# 32.net
KiCad netlist of a schematic drawn in Altium Designer
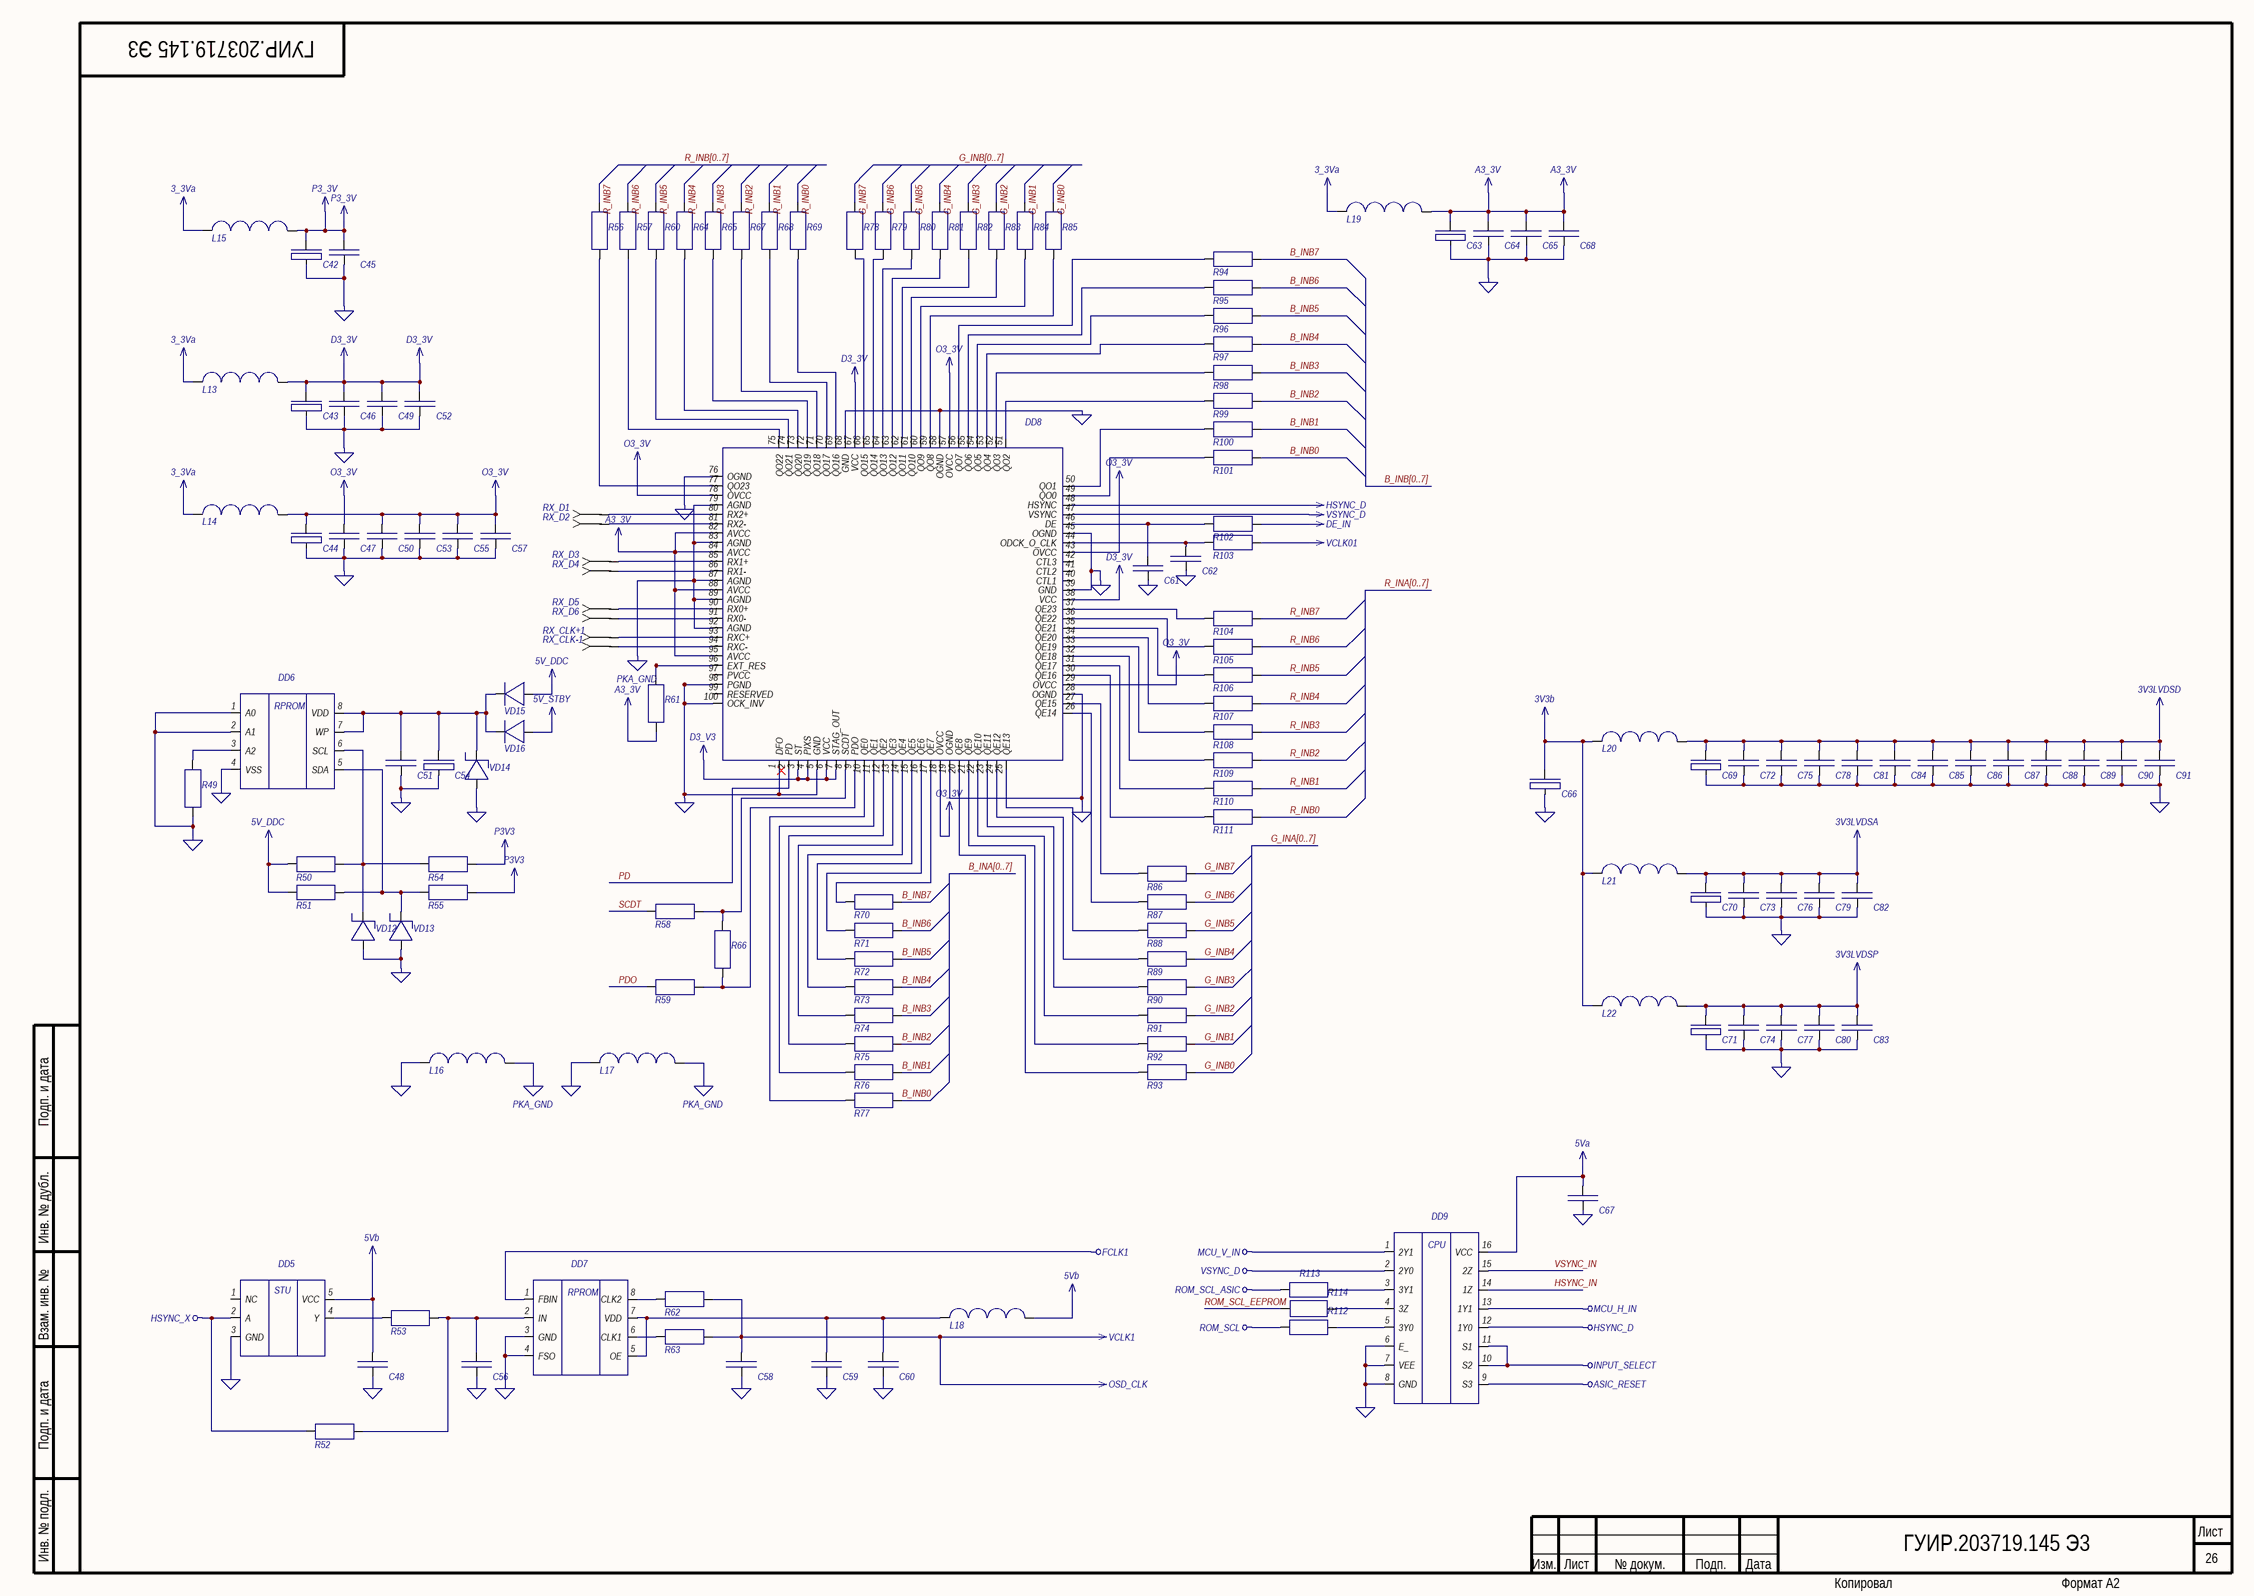
[diagram p0: 32.SchDoc]

(export (version "E")
  (design (tool "Eeschema 10.0.6"))
  (components
    (comp (ref "C42")
      (value "TuningCapacitor")
      (footprint "31_lib:Cap_tantal_D")
      (libsource (lib "31_lib") (part "TuningCapacitor"))
    )
    (comp (ref "C43")
      (value "TuningCapacitor")
      (footprint "31_lib:Cap_tantal_D")
      (libsource (lib "31_lib") (part "TuningCapacitor"))
    )
    (comp (ref "C44")
      (value "TuningCapacitor")
      (footprint "31_lib:Cap_tantal_D")
      (libsource (lib "31_lib") (part "TuningCapacitor"))
    )
    (comp (ref "C45")
      (value "Capacitor")
      (footprint "cap_electro_13")
      (libsource (lib "31_lib") (part "Capacitor"))
    )
    (comp (ref "C46")
      (value "Capacitor")
      (footprint "cap_electro_13")
      (libsource (lib "31_lib") (part "Capacitor"))
    )
    (comp (ref "C47")
      (value "Capacitor")
      (footprint "cap_electro_13")
      (libsource (lib "31_lib") (part "Capacitor"))
    )
    (comp (ref "C48")
      (value "Capacitor")
      (footprint "cap_electro_13")
      (libsource (lib "31_lib") (part "Capacitor"))
    )
    (comp (ref "C49")
      (value "Capacitor")
      (footprint "cap_electro_13")
      (libsource (lib "31_lib") (part "Capacitor"))
    )
    (comp (ref "C50")
      (value "Capacitor")
      (footprint "cap_electro_13")
      (libsource (lib "31_lib") (part "Capacitor"))
    )
    (comp (ref "C51")
      (value "Capacitor")
      (footprint "cap_electro_13")
      (libsource (lib "31_lib") (part "Capacitor"))
    )
    (comp (ref "C52")
      (value "Capacitor")
      (footprint "cap_electro_13")
      (libsource (lib "31_lib") (part "Capacitor"))
    )
    (comp (ref "C53")
      (value "Capacitor")
      (footprint "cap_electro_13")
      (libsource (lib "31_lib") (part "Capacitor"))
    )
    (comp (ref "C54")
      (value "TuningCapacitor")
      (footprint "31_lib:Cap_tantal_D")
      (libsource (lib "31_lib") (part "TuningCapacitor"))
    )
    (comp (ref "C55")
      (value "Capacitor")
      (footprint "cap_electro_13")
      (libsource (lib "31_lib") (part "Capacitor"))
    )
    (comp (ref "C56")
      (value "Capacitor")
      (footprint "cap_electro_13")
      (libsource (lib "31_lib") (part "Capacitor"))
    )
    (comp (ref "C57")
      (value "Capacitor")
      (footprint "cap_electro_13")
      (libsource (lib "31_lib") (part "Capacitor"))
    )
    (comp (ref "C58")
      (value "Capacitor")
      (footprint "cap_electro_13")
      (libsource (lib "31_lib") (part "Capacitor"))
    )
    (comp (ref "C59")
      (value "Capacitor")
      (footprint "cap_electro_13")
      (libsource (lib "31_lib") (part "Capacitor"))
    )
    (comp (ref "C60")
      (value "Capacitor")
      (footprint "cap_electro_13")
      (libsource (lib "31_lib") (part "Capacitor"))
    )
    (comp (ref "C61")
      (value "Capacitor")
      (footprint "cap_electro_13")
      (libsource (lib "31_lib") (part "Capacitor"))
    )
    (comp (ref "C62")
      (value "Capacitor")
      (footprint "cap_electro_13")
      (libsource (lib "31_lib") (part "Capacitor"))
    )
    (comp (ref "C63")
      (value "TuningCapacitor")
      (footprint "31_lib:Cap_tantal_D")
      (libsource (lib "31_lib") (part "TuningCapacitor"))
    )
    (comp (ref "C64")
      (value "Capacitor")
      (footprint "cap_electro_13")
      (libsource (lib "31_lib") (part "Capacitor"))
    )
    (comp (ref "C65")
      (value "Capacitor")
      (footprint "cap_electro_13")
      (libsource (lib "31_lib") (part "Capacitor"))
    )
    (comp (ref "C66")
      (value "TuningCapacitor")
      (footprint "31_lib:Cap_tantal_D")
      (libsource (lib "31_lib") (part "TuningCapacitor"))
    )
    (comp (ref "C67")
      (value "Capacitor")
      (footprint "cap_electro_13")
      (libsource (lib "31_lib") (part "Capacitor"))
    )
    (comp (ref "C68")
      (value "Capacitor")
      (footprint "cap_electro_13")
      (libsource (lib "31_lib") (part "Capacitor"))
    )
    (comp (ref "C69")
      (value "TuningCapacitor")
      (footprint "31_lib:Cap_tantal_D")
      (libsource (lib "31_lib") (part "TuningCapacitor"))
    )
    (comp (ref "C70")
      (value "TuningCapacitor")
      (footprint "31_lib:Cap_tantal_D")
      (libsource (lib "31_lib") (part "TuningCapacitor"))
    )
    (comp (ref "C71")
      (value "TuningCapacitor")
      (footprint "31_lib:Cap_tantal_D")
      (libsource (lib "31_lib") (part "TuningCapacitor"))
    )
    (comp (ref "C72")
      (value "Capacitor")
      (footprint "cap_electro_13")
      (libsource (lib "31_lib") (part "Capacitor"))
    )
    (comp (ref "C73")
      (value "Capacitor")
      (footprint "cap_electro_13")
      (libsource (lib "31_lib") (part "Capacitor"))
    )
    (comp (ref "C74")
      (value "Capacitor")
      (footprint "cap_electro_13")
      (libsource (lib "31_lib") (part "Capacitor"))
    )
    (comp (ref "C75")
      (value "Capacitor")
      (footprint "cap_electro_13")
      (libsource (lib "31_lib") (part "Capacitor"))
    )
    (comp (ref "C76")
      (value "Capacitor")
      (footprint "cap_electro_13")
      (libsource (lib "31_lib") (part "Capacitor"))
    )
    (comp (ref "C77")
      (value "Capacitor")
      (footprint "cap_electro_13")
      (libsource (lib "31_lib") (part "Capacitor"))
    )
    (comp (ref "C78")
      (value "Capacitor")
      (footprint "cap_electro_13")
      (libsource (lib "31_lib") (part "Capacitor"))
    )
    (comp (ref "C79")
      (value "Capacitor")
      (footprint "cap_electro_13")
      (libsource (lib "31_lib") (part "Capacitor"))
    )
    (comp (ref "C80")
      (value "Capacitor")
      (footprint "cap_electro_13")
      (libsource (lib "31_lib") (part "Capacitor"))
    )
    (comp (ref "C81")
      (value "Capacitor")
      (footprint "cap_electro_13")
      (libsource (lib "31_lib") (part "Capacitor"))
    )
    (comp (ref "C82")
      (value "Capacitor")
      (footprint "cap_electro_13")
      (libsource (lib "31_lib") (part "Capacitor"))
    )
    (comp (ref "C83")
      (value "Capacitor")
      (footprint "cap_electro_13")
      (libsource (lib "31_lib") (part "Capacitor"))
    )
    (comp (ref "C84")
      (value "Capacitor")
      (footprint "cap_electro_13")
      (libsource (lib "31_lib") (part "Capacitor"))
    )
    (comp (ref "C85")
      (value "Capacitor")
      (footprint "cap_electro_13")
      (libsource (lib "31_lib") (part "Capacitor"))
    )
    (comp (ref "C86")
      (value "Capacitor")
      (footprint "cap_electro_13")
      (libsource (lib "31_lib") (part "Capacitor"))
    )
    (comp (ref "C87")
      (value "Capacitor")
      (footprint "cap_electro_13")
      (libsource (lib "31_lib") (part "Capacitor"))
    )
    (comp (ref "C88")
      (value "Capacitor")
      (footprint "cap_electro_13")
      (libsource (lib "31_lib") (part "Capacitor"))
    )
    (comp (ref "C89")
      (value "Capacitor")
      (footprint "cap_electro_13")
      (libsource (lib "31_lib") (part "Capacitor"))
    )
    (comp (ref "C90")
      (value "Capacitor")
      (footprint "cap_electro_13")
      (libsource (lib "31_lib") (part "Capacitor"))
    )
    (comp (ref "C91")
      (value "Capacitor")
      (footprint "cap_electro_13")
      (libsource (lib "31_lib") (part "Capacitor"))
    )
    (comp (ref "DD5")
      (value "F14-SINGLE")
      (footprint "74AHC1G14(SOT25)")
      (libsource (lib "31_lib") (part "74AHC1G14-TA"))
    )
    (comp (ref "DD6") (value "24C02") (footprint "31_lib:24Cxx") (libsource (lib "31_lib") (part "24C02")))
    (comp (ref "DD7")
      (value "AV9173-01")
      (footprint "31_lib:AV9173-01(DIP8)")
      (libsource (lib "31_lib") (part "AV9173-01"))
    )
    (comp (ref "DD8") (value "SIL151") (footprint "31_lib:SIL151") (libsource (lib "31_lib") (part "SIL151")))
    (comp (ref "DD9")
      (value "74LV4053")
      (footprint "31_lib:74LV4053(SOT38-4)")
      (libsource (lib "31_lib") (part "74LV4053"))
    )
    (comp (ref "L13")
      (value "Inductor")
      (footprint "31_lib:inductor")
      (libsource (lib "31_lib") (part "Inductor"))
    )
    (comp (ref "L14")
      (value "Inductor")
      (footprint "31_lib:inductor")
      (libsource (lib "31_lib") (part "Inductor"))
    )
    (comp (ref "L15")
      (value "Inductor")
      (footprint "31_lib:inductor")
      (libsource (lib "31_lib") (part "Inductor"))
    )
    (comp (ref "L16")
      (value "Inductor")
      (footprint "31_lib:inductor")
      (libsource (lib "31_lib") (part "Inductor"))
    )
    (comp (ref "L17")
      (value "Inductor")
      (footprint "31_lib:inductor")
      (libsource (lib "31_lib") (part "Inductor"))
    )
    (comp (ref "L18")
      (value "Inductor")
      (footprint "31_lib:inductor")
      (libsource (lib "31_lib") (part "Inductor"))
    )
    (comp (ref "L19")
      (value "Inductor")
      (footprint "31_lib:inductor")
      (libsource (lib "31_lib") (part "Inductor"))
    )
    (comp (ref "L20")
      (value "Inductor")
      (footprint "31_lib:inductor")
      (libsource (lib "31_lib") (part "Inductor"))
    )
    (comp (ref "L21")
      (value "Inductor")
      (footprint "31_lib:inductor")
      (libsource (lib "31_lib") (part "Inductor"))
    )
    (comp (ref "L22")
      (value "Inductor")
      (footprint "31_lib:inductor")
      (libsource (lib "31_lib") (part "Inductor"))
    )
    (comp (ref "R49")
      (value "Resistor")
      (footprint "lab_7_footprints:R_1206")
      (libsource (lib "31_lib") (part "Resistor"))
    )
    (comp (ref "R50")
      (value "Resistor")
      (footprint "lab_7_footprints:R_1206")
      (libsource (lib "31_lib") (part "Resistor"))
    )
    (comp (ref "R51")
      (value "Resistor")
      (footprint "lab_7_footprints:R_1206")
      (libsource (lib "31_lib") (part "Resistor"))
    )
    (comp (ref "R52")
      (value "Resistor")
      (footprint "lab_7_footprints:R_1206")
      (libsource (lib "31_lib") (part "Resistor"))
    )
    (comp (ref "R53")
      (value "Resistor")
      (footprint "lab_7_footprints:R_1206")
      (libsource (lib "31_lib") (part "Resistor"))
    )
    (comp (ref "R54")
      (value "Resistor")
      (footprint "lab_7_footprints:R_1206")
      (libsource (lib "31_lib") (part "Resistor"))
    )
    (comp (ref "R55")
      (value "Resistor")
      (footprint "lab_7_footprints:R_1206")
      (libsource (lib "31_lib") (part "Resistor"))
    )
    (comp (ref "R56")
      (value "Resistor")
      (footprint "lab_7_footprints:R_1206")
      (libsource (lib "31_lib") (part "Resistor"))
    )
    (comp (ref "R57")
      (value "Resistor")
      (footprint "lab_7_footprints:R_1206")
      (libsource (lib "31_lib") (part "Resistor"))
    )
    (comp (ref "R58")
      (value "Resistor")
      (footprint "lab_7_footprints:R_1206")
      (libsource (lib "31_lib") (part "Resistor"))
    )
    (comp (ref "R59")
      (value "Resistor")
      (footprint "lab_7_footprints:R_1206")
      (libsource (lib "31_lib") (part "Resistor"))
    )
    (comp (ref "R60")
      (value "Resistor")
      (footprint "lab_7_footprints:R_1206")
      (libsource (lib "31_lib") (part "Resistor"))
    )
    (comp (ref "R61")
      (value "Resistor")
      (footprint "lab_7_footprints:R_1206")
      (libsource (lib "31_lib") (part "Resistor"))
    )
    (comp (ref "R62")
      (value "Resistor")
      (footprint "lab_7_footprints:R_1206")
      (libsource (lib "31_lib") (part "Resistor"))
    )
    (comp (ref "R63")
      (value "Resistor")
      (footprint "lab_7_footprints:R_1206")
      (libsource (lib "31_lib") (part "Resistor"))
    )
    (comp (ref "R64")
      (value "Resistor")
      (footprint "lab_7_footprints:R_1206")
      (libsource (lib "31_lib") (part "Resistor"))
    )
    (comp (ref "R65")
      (value "Resistor")
      (footprint "lab_7_footprints:R_1206")
      (libsource (lib "31_lib") (part "Resistor"))
    )
    (comp (ref "R66")
      (value "Resistor")
      (footprint "lab_7_footprints:R_1206")
      (libsource (lib "31_lib") (part "Resistor"))
    )
    (comp (ref "R67")
      (value "Resistor")
      (footprint "lab_7_footprints:R_1206")
      (libsource (lib "31_lib") (part "Resistor"))
    )
    (comp (ref "R68")
      (value "Resistor")
      (footprint "lab_7_footprints:R_1206")
      (libsource (lib "31_lib") (part "Resistor"))
    )
    (comp (ref "R69")
      (value "Resistor")
      (footprint "lab_7_footprints:R_1206")
      (libsource (lib "31_lib") (part "Resistor"))
    )
    (comp (ref "R70")
      (value "Resistor")
      (footprint "lab_7_footprints:R_1206")
      (libsource (lib "31_lib") (part "Resistor"))
    )
    (comp (ref "R71")
      (value "Resistor")
      (footprint "lab_7_footprints:R_1206")
      (libsource (lib "31_lib") (part "Resistor"))
    )
    (comp (ref "R72")
      (value "Resistor")
      (footprint "lab_7_footprints:R_1206")
      (libsource (lib "31_lib") (part "Resistor"))
    )
    (comp (ref "R73")
      (value "Resistor")
      (footprint "lab_7_footprints:R_1206")
      (libsource (lib "31_lib") (part "Resistor"))
    )
    (comp (ref "R74")
      (value "Resistor")
      (footprint "lab_7_footprints:R_1206")
      (libsource (lib "31_lib") (part "Resistor"))
    )
    (comp (ref "R75")
      (value "Resistor")
      (footprint "lab_7_footprints:R_1206")
      (libsource (lib "31_lib") (part "Resistor"))
    )
    (comp (ref "R76")
      (value "Resistor")
      (footprint "lab_7_footprints:R_1206")
      (libsource (lib "31_lib") (part "Resistor"))
    )
    (comp (ref "R77")
      (value "Resistor")
      (footprint "lab_7_footprints:R_1206")
      (libsource (lib "31_lib") (part "Resistor"))
    )
    (comp (ref "R78")
      (value "Resistor")
      (footprint "lab_7_footprints:R_1206")
      (libsource (lib "31_lib") (part "Resistor"))
    )
    (comp (ref "R79")
      (value "Resistor")
      (footprint "lab_7_footprints:R_1206")
      (libsource (lib "31_lib") (part "Resistor"))
    )
    (comp (ref "R80")
      (value "Resistor")
      (footprint "lab_7_footprints:R_1206")
      (libsource (lib "31_lib") (part "Resistor"))
    )
    (comp (ref "R81")
      (value "Resistor")
      (footprint "lab_7_footprints:R_1206")
      (libsource (lib "31_lib") (part "Resistor"))
    )
    (comp (ref "R82")
      (value "Resistor")
      (footprint "lab_7_footprints:R_1206")
      (libsource (lib "31_lib") (part "Resistor"))
    )
    (comp (ref "R83")
      (value "Resistor")
      (footprint "lab_7_footprints:R_1206")
      (libsource (lib "31_lib") (part "Resistor"))
    )
    (comp (ref "R84")
      (value "Resistor")
      (footprint "lab_7_footprints:R_1206")
      (libsource (lib "31_lib") (part "Resistor"))
    )
    (comp (ref "R85")
      (value "Resistor")
      (footprint "lab_7_footprints:R_1206")
      (libsource (lib "31_lib") (part "Resistor"))
    )
    (comp (ref "R86")
      (value "Resistor")
      (footprint "lab_7_footprints:R_1206")
      (libsource (lib "31_lib") (part "Resistor"))
    )
    (comp (ref "R87")
      (value "Resistor")
      (footprint "lab_7_footprints:R_1206")
      (libsource (lib "31_lib") (part "Resistor"))
    )
    (comp (ref "R88")
      (value "Resistor")
      (footprint "lab_7_footprints:R_1206")
      (libsource (lib "31_lib") (part "Resistor"))
    )
    (comp (ref "R89")
      (value "Resistor")
      (footprint "lab_7_footprints:R_1206")
      (libsource (lib "31_lib") (part "Resistor"))
    )
    (comp (ref "R90")
      (value "Resistor")
      (footprint "lab_7_footprints:R_1206")
      (libsource (lib "31_lib") (part "Resistor"))
    )
    (comp (ref "R91")
      (value "Resistor")
      (footprint "lab_7_footprints:R_1206")
      (libsource (lib "31_lib") (part "Resistor"))
    )
    (comp (ref "R92")
      (value "Resistor")
      (footprint "lab_7_footprints:R_1206")
      (libsource (lib "31_lib") (part "Resistor"))
    )
    (comp (ref "R93")
      (value "Resistor")
      (footprint "lab_7_footprints:R_1206")
      (libsource (lib "31_lib") (part "Resistor"))
    )
    (comp (ref "R94")
      (value "Resistor")
      (footprint "lab_7_footprints:R_1206")
      (libsource (lib "31_lib") (part "Resistor"))
    )
    (comp (ref "R95")
      (value "Resistor")
      (footprint "lab_7_footprints:R_1206")
      (libsource (lib "31_lib") (part "Resistor"))
    )
    (comp (ref "R96")
      (value "Resistor")
      (footprint "lab_7_footprints:R_1206")
      (libsource (lib "31_lib") (part "Resistor"))
    )
    (comp (ref "R97")
      (value "Resistor")
      (footprint "lab_7_footprints:R_1206")
      (libsource (lib "31_lib") (part "Resistor"))
    )
    (comp (ref "R98")
      (value "Resistor")
      (footprint "lab_7_footprints:R_1206")
      (libsource (lib "31_lib") (part "Resistor"))
    )
    (comp (ref "R99")
      (value "Resistor")
      (footprint "lab_7_footprints:R_1206")
      (libsource (lib "31_lib") (part "Resistor"))
    )
    (comp (ref "R100")
      (value "Resistor")
      (footprint "lab_7_footprints:R_1206")
      (libsource (lib "31_lib") (part "Resistor"))
    )
    (comp (ref "R101")
      (value "Resistor")
      (footprint "lab_7_footprints:R_1206")
      (libsource (lib "31_lib") (part "Resistor"))
    )
    (comp (ref "R102")
      (value "Resistor")
      (footprint "lab_7_footprints:R_1206")
      (libsource (lib "31_lib") (part "Resistor"))
    )
    (comp (ref "R103")
      (value "Resistor")
      (footprint "lab_7_footprints:R_1206")
      (libsource (lib "31_lib") (part "Resistor"))
    )
    (comp (ref "R104")
      (value "Resistor")
      (footprint "lab_7_footprints:R_1206")
      (libsource (lib "31_lib") (part "Resistor"))
    )
    (comp (ref "R105")
      (value "Resistor")
      (footprint "lab_7_footprints:R_1206")
      (libsource (lib "31_lib") (part "Resistor"))
    )
    (comp (ref "R106")
      (value "Resistor")
      (footprint "lab_7_footprints:R_1206")
      (libsource (lib "31_lib") (part "Resistor"))
    )
    (comp (ref "R107")
      (value "Resistor")
      (footprint "lab_7_footprints:R_1206")
      (libsource (lib "31_lib") (part "Resistor"))
    )
    (comp (ref "R108")
      (value "Resistor")
      (footprint "lab_7_footprints:R_1206")
      (libsource (lib "31_lib") (part "Resistor"))
    )
    (comp (ref "R109")
      (value "Resistor")
      (footprint "lab_7_footprints:R_1206")
      (libsource (lib "31_lib") (part "Resistor"))
    )
    (comp (ref "R110")
      (value "Resistor")
      (footprint "lab_7_footprints:R_1206")
      (libsource (lib "31_lib") (part "Resistor"))
    )
    (comp (ref "R111")
      (value "Resistor")
      (footprint "lab_7_footprints:R_1206")
      (libsource (lib "31_lib") (part "Resistor"))
    )
    (comp (ref "R112")
      (value "Resistor")
      (footprint "lab_7_footprints:R_1206")
      (libsource (lib "31_lib") (part "Resistor"))
    )
    (comp (ref "R113")
      (value "Resistor")
      (footprint "lab_7_footprints:R_1206")
      (libsource (lib "31_lib") (part "Resistor"))
    )
    (comp (ref "R114")
      (value "Resistor")
      (footprint "lab_7_footprints:R_1206")
      (libsource (lib "31_lib") (part "Resistor"))
    )
    (comp (ref "RX_CLK+1")
      (value "InputArrow")
      (footprint "31_lib:ARROW")
      (libsource (lib "31_lib") (part "InputArrow"))
    )
    (comp (ref "RX_CLK-1")
      (value "InputArrow")
      (footprint "31_lib:ARROW")
      (libsource (lib "31_lib") (part "InputArrow"))
    )
    (comp (ref "RX_D1")
      (value "InputArrow")
      (footprint "31_lib:ARROW")
      (libsource (lib "31_lib") (part "InputArrow"))
    )
    (comp (ref "RX_D2")
      (value "InputArrow")
      (footprint "31_lib:ARROW")
      (libsource (lib "31_lib") (part "InputArrow"))
    )
    (comp (ref "RX_D3")
      (value "InputArrow")
      (footprint "31_lib:ARROW")
      (libsource (lib "31_lib") (part "InputArrow"))
    )
    (comp (ref "RX_D4")
      (value "InputArrow")
      (footprint "31_lib:ARROW")
      (libsource (lib "31_lib") (part "InputArrow"))
    )
    (comp (ref "RX_D5")
      (value "InputArrow")
      (footprint "31_lib:ARROW")
      (libsource (lib "31_lib") (part "InputArrow"))
    )
    (comp (ref "RX_D6")
      (value "InputArrow")
      (footprint "31_lib:ARROW")
      (libsource (lib "31_lib") (part "InputArrow"))
    )
    (comp (ref "VD12")
      (value "DiodeSchottky")
      (footprint "lab_7_footprints:zener_diode")
      (libsource (lib "31_lib") (part "DiodeSchottky"))
    )
    (comp (ref "VD13")
      (value "DiodeSchottky")
      (footprint "lab_7_footprints:zener_diode")
      (libsource (lib "31_lib") (part "DiodeSchottky"))
    )
    (comp (ref "VD14")
      (value "DiodeSchottky")
      (footprint "lab_7_footprints:zener_diode")
      (libsource (lib "31_lib") (part "DiodeSchottky"))
    )
    (comp (ref "VD15")
      (value "Diode")
      (footprint "lab_7_footprints:zener_diode")
      (libsource (lib "31_lib") (part "Diode"))
    )
    (comp (ref "VD16")
      (value "Diode")
      (footprint "lab_7_footprints:zener_diode")
      (libsource (lib "31_lib") (part "Diode"))
    )
  )
  (nets
    (net (code "26") (name "/B_INB0") (class "Default")
      (node (ref "R101") (pin "2") (pinfunction "2_2") (pintype "passive"))
      (node (ref "R77") (pin "2") (pinfunction "2_2") (pintype "passive"))
    )
    (net (code "27") (name "/B_INB1") (class "Default")
      (node (ref "R100") (pin "2") (pinfunction "2_2") (pintype "passive"))
      (node (ref "R76") (pin "2") (pinfunction "2_2") (pintype "passive"))
    )
    (net (code "28") (name "/B_INB2") (class "Default")
      (node (ref "R75") (pin "2") (pinfunction "2_2") (pintype "passive"))
      (node (ref "R99") (pin "2") (pinfunction "2_2") (pintype "passive"))
    )
    (net (code "29") (name "/B_INB3") (class "Default")
      (node (ref "R74") (pin "2") (pinfunction "2_2") (pintype "passive"))
      (node (ref "R98") (pin "2") (pinfunction "2_2") (pintype "passive"))
    )
    (net (code "30") (name "/B_INB4") (class "Default")
      (node (ref "R73") (pin "2") (pinfunction "2_2") (pintype "passive"))
      (node (ref "R97") (pin "2") (pinfunction "2_2") (pintype "passive"))
    )
    (net (code "31") (name "/B_INB5") (class "Default")
      (node (ref "R72") (pin "2") (pinfunction "2_2") (pintype "passive"))
      (node (ref "R96") (pin "2") (pinfunction "2_2") (pintype "passive"))
    )
    (net (code "32") (name "/B_INB6") (class "Default")
      (node (ref "R71") (pin "2") (pinfunction "2_2") (pintype "passive"))
      (node (ref "R95") (pin "2") (pinfunction "2_2") (pintype "passive"))
    )
    (net (code "33") (name "/B_INB7") (class "Default")
      (node (ref "R70") (pin "2") (pinfunction "2_2") (pintype "passive"))
      (node (ref "R94") (pin "2") (pinfunction "2_2") (pintype "passive"))
    )
    (net (code "36") (name "/G_INB0") (class "Default")
      (node (ref "R85") (pin "2") (pinfunction "2_2") (pintype "passive"))
      (node (ref "R93") (pin "2") (pinfunction "2_2") (pintype "passive"))
    )
    (net (code "37") (name "/G_INB1") (class "Default")
      (node (ref "R84") (pin "2") (pinfunction "2_2") (pintype "passive"))
      (node (ref "R92") (pin "2") (pinfunction "2_2") (pintype "passive"))
    )
    (net (code "38") (name "/G_INB2") (class "Default")
      (node (ref "R83") (pin "2") (pinfunction "2_2") (pintype "passive"))
      (node (ref "R91") (pin "2") (pinfunction "2_2") (pintype "passive"))
    )
    (net (code "39") (name "/G_INB3") (class "Default")
      (node (ref "R82") (pin "2") (pinfunction "2_2") (pintype "passive"))
      (node (ref "R90") (pin "2") (pinfunction "2_2") (pintype "passive"))
    )
    (net (code "40") (name "/G_INB4") (class "Default")
      (node (ref "R81") (pin "2") (pinfunction "2_2") (pintype "passive"))
      (node (ref "R89") (pin "2") (pinfunction "2_2") (pintype "passive"))
    )
    (net (code "41") (name "/G_INB5") (class "Default")
      (node (ref "R80") (pin "2") (pinfunction "2_2") (pintype "passive"))
      (node (ref "R88") (pin "2") (pinfunction "2_2") (pintype "passive"))
    )
    (net (code "42") (name "/G_INB6") (class "Default")
      (node (ref "R79") (pin "2") (pinfunction "2_2") (pintype "passive"))
      (node (ref "R87") (pin "2") (pinfunction "2_2") (pintype "passive"))
    )
    (net (code "43") (name "/G_INB7") (class "Default")
      (node (ref "R78") (pin "2") (pinfunction "2_2") (pintype "passive"))
      (node (ref "R86") (pin "2") (pinfunction "2_2") (pintype "passive"))
    )
    (net (code "44") (name "/HSYNC_IN") (class "Default")
      (node (ref "DD9") (pin "14") (pinfunction "1Z_14") (pintype "passive"))
    )
    (net (code "45") (name "/PD") (class "Default")
      (node (ref "DD8") (pin "2") (pinfunction "PD_2") (pintype "passive"))
    )
    (net (code "46") (name "/PDO") (class "Default")
      (node (ref "R59") (pin "2") (pinfunction "2_2") (pintype "passive"))
    )
    (net (code "47") (name "/ROM_SCL_EEPROM") (class "Default")
      (node (ref "R114") (pin "2") (pinfunction "2_2") (pintype "passive"))
    )
    (net (code "49") (name "/R_INB0") (class "Default")
      (node (ref "R111") (pin "2") (pinfunction "2_2") (pintype "passive"))
      (node (ref "R69") (pin "2") (pinfunction "2_2") (pintype "passive"))
    )
    (net (code "50") (name "/R_INB1") (class "Default")
      (node (ref "R110") (pin "2") (pinfunction "2_2") (pintype "passive"))
      (node (ref "R68") (pin "2") (pinfunction "2_2") (pintype "passive"))
    )
    (net (code "51") (name "/R_INB2") (class "Default")
      (node (ref "R109") (pin "2") (pinfunction "2_2") (pintype "passive"))
      (node (ref "R67") (pin "2") (pinfunction "2_2") (pintype "passive"))
    )
    (net (code "52") (name "/R_INB3") (class "Default")
      (node (ref "R108") (pin "2") (pinfunction "2_2") (pintype "passive"))
      (node (ref "R65") (pin "2") (pinfunction "2_2") (pintype "passive"))
    )
    (net (code "53") (name "/R_INB4") (class "Default")
      (node (ref "R107") (pin "2") (pinfunction "2_2") (pintype "passive"))
      (node (ref "R64") (pin "2") (pinfunction "2_2") (pintype "passive"))
    )
    (net (code "54") (name "/R_INB5") (class "Default")
      (node (ref "R106") (pin "2") (pinfunction "2_2") (pintype "passive"))
      (node (ref "R60") (pin "2") (pinfunction "2_2") (pintype "passive"))
    )
    (net (code "55") (name "/R_INB6") (class "Default")
      (node (ref "R105") (pin "2") (pinfunction "2_2") (pintype "passive"))
      (node (ref "R57") (pin "2") (pinfunction "2_2") (pintype "passive"))
    )
    (net (code "56") (name "/R_INB7") (class "Default")
      (node (ref "R104") (pin "2") (pinfunction "2_2") (pintype "passive"))
      (node (ref "R56") (pin "2") (pinfunction "2_2") (pintype "passive"))
    )
    (net (code "58") (name "/SCDT") (class "Default")
      (node (ref "R58") (pin "2") (pinfunction "2_2") (pintype "passive"))
    )
    (net (code "59") (name "/VSYNC_IN") (class "Default")
      (node (ref "DD9") (pin "15") (pinfunction "2Z_15") (pintype "passive"))
    )
    (net (code "60") (name "3V3LVDSA") (class "Default")
      (node (ref "C70") (pin "1") (pinfunction "1_1") (pintype "passive"))
      (node (ref "C73") (pin "2") (pinfunction "2_2") (pintype "passive"))
      (node (ref "C76") (pin "2") (pinfunction "2_2") (pintype "passive"))
      (node (ref "C79") (pin "2") (pinfunction "2_2") (pintype "passive"))
      (node (ref "C82") (pin "2") (pinfunction "2_2") (pintype "passive"))
      (node (ref "L21") (pin "2") (pinfunction "2_2") (pintype "passive"))
    )
    (net (code "61") (name "3V3LVDSD") (class "Default")
      (node (ref "C69") (pin "1") (pinfunction "1_1") (pintype "passive"))
      (node (ref "C72") (pin "2") (pinfunction "2_2") (pintype "passive"))
      (node (ref "C75") (pin "2") (pinfunction "2_2") (pintype "passive"))
      (node (ref "C78") (pin "2") (pinfunction "2_2") (pintype "passive"))
      (node (ref "C81") (pin "2") (pinfunction "2_2") (pintype "passive"))
      (node (ref "C84") (pin "2") (pinfunction "2_2") (pintype "passive"))
      (node (ref "C85") (pin "2") (pinfunction "2_2") (pintype "passive"))
      (node (ref "C86") (pin "2") (pinfunction "2_2") (pintype "passive"))
      (node (ref "C87") (pin "2") (pinfunction "2_2") (pintype "passive"))
      (node (ref "C88") (pin "2") (pinfunction "2_2") (pintype "passive"))
      (node (ref "C89") (pin "2") (pinfunction "2_2") (pintype "passive"))
      (node (ref "C90") (pin "2") (pinfunction "2_2") (pintype "passive"))
      (node (ref "C91") (pin "2") (pinfunction "2_2") (pintype "passive"))
      (node (ref "L20") (pin "2") (pinfunction "2_2") (pintype "passive"))
    )
    (net (code "62") (name "3V3LVDSP") (class "Default")
      (node (ref "C71") (pin "1") (pinfunction "1_1") (pintype "passive"))
      (node (ref "C74") (pin "2") (pinfunction "2_2") (pintype "passive"))
      (node (ref "C77") (pin "2") (pinfunction "2_2") (pintype "passive"))
      (node (ref "C80") (pin "2") (pinfunction "2_2") (pintype "passive"))
      (node (ref "C83") (pin "2") (pinfunction "2_2") (pintype "passive"))
      (node (ref "L22") (pin "2") (pinfunction "2_2") (pintype "passive"))
    )
    (net (code "63") (name "3V3b") (class "Default")
      (node (ref "C66") (pin "1") (pinfunction "1_1") (pintype "passive"))
      (node (ref "L20") (pin "1") (pinfunction "1_1") (pintype "passive"))
      (node (ref "L21") (pin "1") (pinfunction "1_1") (pintype "passive"))
      (node (ref "L22") (pin "1") (pinfunction "1_1") (pintype "passive"))
    )
    (net (code "64") (name "3_3Va") (class "Default")
      (node (ref "L13") (pin "1") (pinfunction "1_1") (pintype "passive"))
      (node (ref "L14") (pin "1") (pinfunction "1_1") (pintype "passive"))
      (node (ref "L15") (pin "1") (pinfunction "1_1") (pintype "passive"))
      (node (ref "L19") (pin "1") (pinfunction "1_1") (pintype "passive"))
    )
    (net (code "65") (name "5V_DDC") (class "Default")
      (node (ref "R50") (pin "2") (pinfunction "2_2") (pintype "passive"))
      (node (ref "R51") (pin "2") (pinfunction "2_2") (pintype "passive"))
      (node (ref "VD15") (pin "1") (pinfunction "1_1") (pintype "passive"))
    )
    (net (code "66") (name "5V_STBY") (class "Default")
      (node (ref "VD16") (pin "1") (pinfunction "1_1") (pintype "passive"))
    )
    (net (code "67") (name "5Va") (class "Default")
      (node (ref "C67") (pin "2") (pinfunction "2_2") (pintype "passive"))
      (node (ref "DD9") (pin "16") (pinfunction "VCC_16") (pintype "passive"))
    )
    (net (code "68") (name "5Vb") (class "Default")
      (node (ref "C48") (pin "1") (pinfunction "1_1") (pintype "passive"))
      (node (ref "DD5") (pin "5") (pinfunction "VCC_5") (pintype "passive"))
      (node (ref "L18") (pin "2") (pinfunction "2_2") (pintype "passive"))
    )
    (net (code "69") (name "A3_3V") (class "Default")
      (node (ref "C63") (pin "1") (pinfunction "1_1") (pintype "passive"))
      (node (ref "C64") (pin "2") (pinfunction "2_2") (pintype "passive"))
      (node (ref "C65") (pin "2") (pinfunction "2_2") (pintype "passive"))
      (node (ref "C68") (pin "2") (pinfunction "2_2") (pintype "passive"))
      (node (ref "DD8") (pin "82") (pinfunction "AVCC_82") (pintype "passive"))
      (node (ref "DD8") (pin "84") (pinfunction "AVCC_84") (pintype "passive"))
      (node (ref "DD8") (pin "88") (pinfunction "AVCC_88") (pintype "passive"))
      (node (ref "DD8") (pin "95") (pinfunction "AVCC_95") (pintype "passive"))
      (node (ref "L19") (pin "2") (pinfunction "2_2") (pintype "passive"))
      (node (ref "R61") (pin "1") (pinfunction "1_1") (pintype "passive"))
    )
    (net (code "70") (name "ASIC_RESET") (class "Default")
      (node (ref "DD9") (pin "9") (pinfunction "S3_9") (pintype "passive"))
    )
    (net (code "71") (name "D3_3V") (class "Default")
      (node (ref "C43") (pin "1") (pinfunction "1_1") (pintype "passive"))
      (node (ref "C46") (pin "2") (pinfunction "2_2") (pintype "passive"))
      (node (ref "C49") (pin "2") (pinfunction "2_2") (pintype "passive"))
      (node (ref "C52") (pin "2") (pinfunction "2_2") (pintype "passive"))
      (node (ref "DD8") (pin "38") (pinfunction "VCC_38") (pintype "passive"))
      (node (ref "DD8") (pin "67") (pinfunction "VCC_67") (pintype "passive"))
      (node (ref "L13") (pin "2") (pinfunction "2_2") (pintype "passive"))
    )
    (net (code "72") (name "D3_V3") (class "Default")
      (node (ref "DD8") (pin "3") (pinfunction "ST_3") (pintype "passive"))
      (node (ref "DD8") (pin "4") (pinfunction "PIXS_4") (pintype "passive"))
      (node (ref "DD8") (pin "6") (pinfunction "VCC_6") (pintype "passive"))
      (node (ref "DD8") (pin "7") (pinfunction "STAG_OUT_7") (pintype "passive"))
    )
    (net (code "73") (name "DE_IN") (class "Default")
      (node (ref "R102") (pin "2") (pinfunction "2_2") (pintype "passive"))
    )
    (net (code "74") (name "FCLK1") (class "Default")
      (node (ref "DD7") (pin "1") (pinfunction "FBIN_1") (pintype "passive"))
    )
    (net (code "75") (name "GND") (class "Default")
      (node (ref "C42") (pin "2") (pinfunction "2_2") (pintype "passive"))
      (node (ref "C43") (pin "2") (pinfunction "2_2") (pintype "passive"))
      (node (ref "C44") (pin "2") (pinfunction "2_2") (pintype "passive"))
      (node (ref "C45") (pin "1") (pinfunction "1_1") (pintype "passive"))
      (node (ref "C46") (pin "1") (pinfunction "1_1") (pintype "passive"))
      (node (ref "C47") (pin "1") (pinfunction "1_1") (pintype "passive"))
      (node (ref "C48") (pin "2") (pinfunction "2_2") (pintype "passive"))
      (node (ref "C49") (pin "1") (pinfunction "1_1") (pintype "passive"))
      (node (ref "C50") (pin "1") (pinfunction "1_1") (pintype "passive"))
      (node (ref "C51") (pin "1") (pinfunction "1_1") (pintype "passive"))
      (node (ref "C52") (pin "1") (pinfunction "1_1") (pintype "passive"))
      (node (ref "C53") (pin "1") (pinfunction "1_1") (pintype "passive"))
      (node (ref "C54") (pin "2") (pinfunction "2_2") (pintype "passive"))
      (node (ref "C55") (pin "1") (pinfunction "1_1") (pintype "passive"))
      (node (ref "C56") (pin "2") (pinfunction "2_2") (pintype "passive"))
      (node (ref "C57") (pin "1") (pinfunction "1_1") (pintype "passive"))
      (node (ref "C58") (pin "2") (pinfunction "2_2") (pintype "passive"))
      (node (ref "C59") (pin "2") (pinfunction "2_2") (pintype "passive"))
      (node (ref "C60") (pin "2") (pinfunction "2_2") (pintype "passive"))
      (node (ref "C61") (pin "1") (pinfunction "1_1") (pintype "passive"))
      (node (ref "C62") (pin "1") (pinfunction "1_1") (pintype "passive"))
      (node (ref "C63") (pin "2") (pinfunction "2_2") (pintype "passive"))
      (node (ref "C64") (pin "1") (pinfunction "1_1") (pintype "passive"))
      (node (ref "C65") (pin "1") (pinfunction "1_1") (pintype "passive"))
      (node (ref "C66") (pin "2") (pinfunction "2_2") (pintype "passive"))
      (node (ref "C67") (pin "1") (pinfunction "1_1") (pintype "passive"))
      (node (ref "C68") (pin "1") (pinfunction "1_1") (pintype "passive"))
      (node (ref "C69") (pin "2") (pinfunction "2_2") (pintype "passive"))
      (node (ref "C70") (pin "2") (pinfunction "2_2") (pintype "passive"))
      (node (ref "C71") (pin "2") (pinfunction "2_2") (pintype "passive"))
      (node (ref "C72") (pin "1") (pinfunction "1_1") (pintype "passive"))
      (node (ref "C73") (pin "1") (pinfunction "1_1") (pintype "passive"))
      (node (ref "C74") (pin "1") (pinfunction "1_1") (pintype "passive"))
      (node (ref "C75") (pin "1") (pinfunction "1_1") (pintype "passive"))
      (node (ref "C76") (pin "1") (pinfunction "1_1") (pintype "passive"))
      (node (ref "C77") (pin "1") (pinfunction "1_1") (pintype "passive"))
      (node (ref "C78") (pin "1") (pinfunction "1_1") (pintype "passive"))
      (node (ref "C79") (pin "1") (pinfunction "1_1") (pintype "passive"))
      (node (ref "C80") (pin "1") (pinfunction "1_1") (pintype "passive"))
      (node (ref "C81") (pin "1") (pinfunction "1_1") (pintype "passive"))
      (node (ref "C82") (pin "1") (pinfunction "1_1") (pintype "passive"))
      (node (ref "C83") (pin "1") (pinfunction "1_1") (pintype "passive"))
      (node (ref "C84") (pin "1") (pinfunction "1_1") (pintype "passive"))
      (node (ref "C85") (pin "1") (pinfunction "1_1") (pintype "passive"))
      (node (ref "C86") (pin "1") (pinfunction "1_1") (pintype "passive"))
      (node (ref "C87") (pin "1") (pinfunction "1_1") (pintype "passive"))
      (node (ref "C88") (pin "1") (pinfunction "1_1") (pintype "passive"))
      (node (ref "C89") (pin "1") (pinfunction "1_1") (pintype "passive"))
      (node (ref "C90") (pin "1") (pinfunction "1_1") (pintype "passive"))
      (node (ref "C91") (pin "1") (pinfunction "1_1") (pintype "passive"))
      (node (ref "DD5") (pin "3") (pinfunction "GND_3") (pintype "passive"))
      (node (ref "DD6") (pin "1") (pinfunction "A0_1") (pintype "passive"))
      (node (ref "DD6") (pin "2") (pinfunction "A1_2") (pintype "passive"))
      (node (ref "DD6") (pin "4") (pinfunction "VSS_4") (pintype "passive"))
      (node (ref "DD7") (pin "3") (pinfunction "GND_3") (pintype "passive"))
      (node (ref "DD7") (pin "4") (pinfunction "FSO_4") (pintype "passive"))
      (node (ref "DD8") (pin "1") (pinfunction "DFO_1") (pintype "passive"))
      (node (ref "DD8") (pin "100") (pinfunction "OCK_INV_100") (pintype "passive"))
      (node (ref "DD8") (pin "19") (pinfunction "OGND_19") (pintype "passive"))
      (node (ref "DD8") (pin "28") (pinfunction "OGND_28") (pintype "passive"))
      (node (ref "DD8") (pin "39") (pinfunction "GND_39") (pintype "passive"))
      (node (ref "DD8") (pin "45") (pinfunction "OGND_45") (pintype "passive"))
      (node (ref "DD8") (pin "5") (pinfunction "GND_5") (pintype "passive"))
      (node (ref "DD8") (pin "58") (pinfunction "OGND_58") (pintype "passive"))
      (node (ref "DD8") (pin "68") (pinfunction "GND_68") (pintype "passive"))
      (node (ref "DD8") (pin "76") (pinfunction "OGND_76") (pintype "passive"))
      (node (ref "DD8") (pin "98") (pinfunction "PGND_98") (pintype "passive"))
      (node (ref "DD9") (pin "6") (pinfunction "E__6") (pintype "passive"))
      (node (ref "DD9") (pin "7") (pinfunction "VEE_7") (pintype "passive"))
      (node (ref "DD9") (pin "8") (pinfunction "GND_8") (pintype "passive"))
      (node (ref "L16") (pin "1") (pinfunction "1_1") (pintype "passive"))
      (node (ref "L17") (pin "1") (pinfunction "1_1") (pintype "passive"))
      (node (ref "R49") (pin "1") (pinfunction "1_1") (pintype "passive"))
      (node (ref "VD12") (pin "1") (pinfunction "1_1") (pintype "passive"))
      (node (ref "VD13") (pin "1") (pinfunction "1_1") (pintype "passive"))
      (node (ref "VD14") (pin "1") (pinfunction "1_1") (pintype "passive"))
    )
    (net (code "76") (name "HSYNC_D") (class "Default")
      (node (ref "DD8") (pin "48") (pinfunction "HSYNC_48") (pintype "passive"))
      (node (ref "DD9") (pin "12") (pinfunction "1Y0_12") (pintype "passive"))
    )
    (net (code "77") (name "HSYNC_X") (class "Default")
      (node (ref "DD5") (pin "2") (pinfunction "A_2") (pintype "passive"))
      (node (ref "R52") (pin "1") (pinfunction "1_1") (pintype "passive"))
    )
    (net (code "78") (name "INPUT_SELECT") (class "Default")
      (node (ref "DD9") (pin "10") (pinfunction "S2_10") (pintype "passive"))
      (node (ref "DD9") (pin "11") (pinfunction "S1_11") (pintype "passive"))
    )
    (net (code "79") (name "MCU_H_IN") (class "Default")
      (node (ref "DD9") (pin "13") (pinfunction "1Y1_13") (pintype "passive"))
    )
    (net (code "80") (name "MCU_V_IN") (class "Default")
      (node (ref "DD9") (pin "1") (pinfunction "2Y1_1") (pintype "passive"))
    )
    (net (code "81") (name "Net-(DD5-Y)") (class "Default")
      (node (ref "DD5") (pin "4") (pinfunction "Y_4") (pintype "passive"))
      (node (ref "R53") (pin "1") (pinfunction "1_1") (pintype "passive"))
    )
    (net (code "82") (name "Net-(DD6-A2)") (class "Default")
      (node (ref "DD6") (pin "3") (pinfunction "A2_3") (pintype "passive"))
      (node (ref "R49") (pin "2") (pinfunction "2_2") (pintype "passive"))
    )
    (net (code "83") (name "Net-(DD6-SCL)") (class "Default")
      (node (ref "DD6") (pin "6") (pinfunction "SCL_6") (pintype "passive"))
      (node (ref "R50") (pin "1") (pinfunction "1_1") (pintype "passive"))
      (node (ref "R54") (pin "2") (pinfunction "2_2") (pintype "passive"))
      (node (ref "VD12") (pin "2") (pinfunction "2_2") (pintype "passive"))
    )
    (net (code "84") (name "Net-(DD6-SDA)") (class "Default")
      (node (ref "DD6") (pin "5") (pinfunction "SDA_5") (pintype "passive"))
      (node (ref "R51") (pin "1") (pinfunction "1_1") (pintype "passive"))
      (node (ref "R55") (pin "2") (pinfunction "2_2") (pintype "passive"))
      (node (ref "VD13") (pin "2") (pinfunction "2_2") (pintype "passive"))
    )
    (net (code "85") (name "Net-(DD6-VDD)") (class "Default")
      (node (ref "C51") (pin "2") (pinfunction "2_2") (pintype "passive"))
      (node (ref "C54") (pin "1") (pinfunction "1_1") (pintype "passive"))
      (node (ref "DD6") (pin "7") (pinfunction "WP_7") (pintype "passive"))
      (node (ref "DD6") (pin "8") (pinfunction "VDD_8") (pintype "passive"))
      (node (ref "VD14") (pin "2") (pinfunction "2_2") (pintype "passive"))
      (node (ref "VD15") (pin "2") (pinfunction "2_2") (pintype "passive"))
      (node (ref "VD16") (pin "2") (pinfunction "2_2") (pintype "passive"))
    )
    (net (code "86") (name "Net-(DD7-CLK1)") (class "Default")
      (node (ref "DD7") (pin "6") (pinfunction "CLK1_6") (pintype "passive"))
      (node (ref "R63") (pin "1") (pinfunction "1_1") (pintype "passive"))
    )
    (net (code "87") (name "Net-(DD7-CLK2)") (class "Default")
      (node (ref "DD7") (pin "8") (pinfunction "CLK2_8") (pintype "passive"))
      (node (ref "R62") (pin "1") (pinfunction "1_1") (pintype "passive"))
    )
    (net (code "88") (name "Net-(DD7-IN)") (class "Default")
      (node (ref "C56") (pin "1") (pinfunction "1_1") (pintype "passive"))
      (node (ref "DD7") (pin "2") (pinfunction "IN_2") (pintype "passive"))
      (node (ref "R52") (pin "2") (pinfunction "2_2") (pintype "passive"))
      (node (ref "R53") (pin "2") (pinfunction "2_2") (pintype "passive"))
    )
    (net (code "89") (name "Net-(DD7-OE)") (class "Default")
      (node (ref "C59") (pin "1") (pinfunction "1_1") (pintype "passive"))
      (node (ref "C60") (pin "1") (pinfunction "1_1") (pintype "passive"))
      (node (ref "DD7") (pin "5") (pinfunction "OE_5") (pintype "passive"))
      (node (ref "DD7") (pin "7") (pinfunction "VDD_7") (pintype "passive"))
      (node (ref "L18") (pin "1") (pinfunction "1_1") (pintype "passive"))
    )
    (net (code "90") (name "Net-(DD8-DE)") (class "Default")
      (node (ref "C61") (pin "2") (pinfunction "2_2") (pintype "passive"))
      (node (ref "DD8") (pin "46") (pinfunction "DE_46") (pintype "passive"))
      (node (ref "R102") (pin "1") (pinfunction "1_1") (pintype "passive"))
    )
    (net (code "91") (name "Net-(DD8-EXT_RES)") (class "Default")
      (node (ref "DD8") (pin "96") (pinfunction "EXT_RES_96") (pintype "passive"))
      (node (ref "R61") (pin "2") (pinfunction "2_2") (pintype "passive"))
    )
    (net (code "92") (name "Net-(DD8-ODCK_O_CLK)") (class "Default")
      (node (ref "C62") (pin "2") (pinfunction "2_2") (pintype "passive"))
      (node (ref "DD8") (pin "44") (pinfunction "ODCK_O_CLK_44") (pintype "passive"))
      (node (ref "R103") (pin "1") (pinfunction "1_1") (pintype "passive"))
    )
    (net (code "93") (name "Net-(DD8-PDO)") (class "Default")
      (node (ref "DD8") (pin "9") (pinfunction "PDO_9") (pintype "passive"))
      (node (ref "R59") (pin "1") (pinfunction "1_1") (pintype "passive"))
      (node (ref "R66") (pin "1") (pinfunction "1_1") (pintype "passive"))
    )
    (net (code "94") (name "Net-(DD8-QE0)") (class "Default")
      (node (ref "DD8") (pin "10") (pinfunction "QE0_10") (pintype "passive"))
      (node (ref "R77") (pin "1") (pinfunction "1_1") (pintype "passive"))
    )
    (net (code "95") (name "Net-(DD8-QE1)") (class "Default")
      (node (ref "DD8") (pin "11") (pinfunction "QE1_11") (pintype "passive"))
      (node (ref "R76") (pin "1") (pinfunction "1_1") (pintype "passive"))
    )
    (net (code "96") (name "Net-(DD8-QE2)") (class "Default")
      (node (ref "DD8") (pin "12") (pinfunction "QE2_12") (pintype "passive"))
      (node (ref "R75") (pin "1") (pinfunction "1_1") (pintype "passive"))
    )
    (net (code "97") (name "Net-(DD8-QE3)") (class "Default")
      (node (ref "DD8") (pin "13") (pinfunction "QE3_13") (pintype "passive"))
      (node (ref "R74") (pin "1") (pinfunction "1_1") (pintype "passive"))
    )
    (net (code "98") (name "Net-(DD8-QE4)") (class "Default")
      (node (ref "DD8") (pin "14") (pinfunction "QE4_14") (pintype "passive"))
      (node (ref "R73") (pin "1") (pinfunction "1_1") (pintype "passive"))
    )
    (net (code "99") (name "Net-(DD8-QE5)") (class "Default")
      (node (ref "DD8") (pin "15") (pinfunction "QE5_15") (pintype "passive"))
      (node (ref "R72") (pin "1") (pinfunction "1_1") (pintype "passive"))
    )
    (net (code "100") (name "Net-(DD8-QE6)") (class "Default")
      (node (ref "DD8") (pin "16") (pinfunction "QE6_16") (pintype "passive"))
      (node (ref "R71") (pin "1") (pinfunction "1_1") (pintype "passive"))
    )
    (net (code "101") (name "Net-(DD8-QE7)") (class "Default")
      (node (ref "DD8") (pin "17") (pinfunction "QE7_17") (pintype "passive"))
      (node (ref "R70") (pin "1") (pinfunction "1_1") (pintype "passive"))
    )
    (net (code "102") (name "Net-(DD8-QE8)") (class "Default")
      (node (ref "DD8") (pin "20") (pinfunction "QE8_20") (pintype "passive"))
      (node (ref "R93") (pin "1") (pinfunction "1_1") (pintype "passive"))
    )
    (net (code "103") (name "Net-(DD8-QE9)") (class "Default")
      (node (ref "DD8") (pin "21") (pinfunction "QE9_21") (pintype "passive"))
      (node (ref "R92") (pin "1") (pinfunction "1_1") (pintype "passive"))
    )
    (net (code "104") (name "Net-(DD8-QE10)") (class "Default")
      (node (ref "DD8") (pin "22") (pinfunction "QE10_22") (pintype "passive"))
      (node (ref "R91") (pin "1") (pinfunction "1_1") (pintype "passive"))
    )
    (net (code "105") (name "Net-(DD8-QE11)") (class "Default")
      (node (ref "DD8") (pin "23") (pinfunction "QE11_23") (pintype "passive"))
      (node (ref "R90") (pin "1") (pinfunction "1_1") (pintype "passive"))
    )
    (net (code "106") (name "Net-(DD8-QE12)") (class "Default")
      (node (ref "DD8") (pin "24") (pinfunction "QE12_24") (pintype "passive"))
      (node (ref "R89") (pin "1") (pinfunction "1_1") (pintype "passive"))
    )
    (net (code "107") (name "Net-(DD8-QE13)") (class "Default")
      (node (ref "DD8") (pin "25") (pinfunction "QE13_25") (pintype "passive"))
      (node (ref "R88") (pin "1") (pinfunction "1_1") (pintype "passive"))
    )
    (net (code "108") (name "Net-(DD8-QE14)") (class "Default")
      (node (ref "DD8") (pin "26") (pinfunction "QE14_26") (pintype "passive"))
      (node (ref "R87") (pin "1") (pinfunction "1_1") (pintype "passive"))
    )
    (net (code "109") (name "Net-(DD8-QE15)") (class "Default")
      (node (ref "DD8") (pin "27") (pinfunction "QE15_27") (pintype "passive"))
      (node (ref "R86") (pin "1") (pinfunction "1_1") (pintype "passive"))
    )
    (net (code "110") (name "Net-(DD8-QE16)") (class "Default")
      (node (ref "DD8") (pin "30") (pinfunction "QE16_30") (pintype "passive"))
      (node (ref "R111") (pin "1") (pinfunction "1_1") (pintype "passive"))
    )
    (net (code "111") (name "Net-(DD8-QE17)") (class "Default")
      (node (ref "DD8") (pin "31") (pinfunction "QE17_31") (pintype "passive"))
      (node (ref "R110") (pin "1") (pinfunction "1_1") (pintype "passive"))
    )
    (net (code "112") (name "Net-(DD8-QE18)") (class "Default")
      (node (ref "DD8") (pin "32") (pinfunction "QE18_32") (pintype "passive"))
      (node (ref "R109") (pin "1") (pinfunction "1_1") (pintype "passive"))
    )
    (net (code "113") (name "Net-(DD8-QE19)") (class "Default")
      (node (ref "DD8") (pin "33") (pinfunction "QE19_33") (pintype "passive"))
      (node (ref "R108") (pin "1") (pinfunction "1_1") (pintype "passive"))
    )
    (net (code "114") (name "Net-(DD8-QE20)") (class "Default")
      (node (ref "DD8") (pin "34") (pinfunction "QE20_34") (pintype "passive"))
      (node (ref "R107") (pin "1") (pinfunction "1_1") (pintype "passive"))
    )
    (net (code "115") (name "Net-(DD8-QE21)") (class "Default")
      (node (ref "DD8") (pin "35") (pinfunction "QE21_35") (pintype "passive"))
      (node (ref "R106") (pin "1") (pinfunction "1_1") (pintype "passive"))
    )
    (net (code "116") (name "Net-(DD8-QE22)") (class "Default")
      (node (ref "DD8") (pin "36") (pinfunction "QE22_36") (pintype "passive"))
      (node (ref "R105") (pin "1") (pinfunction "1_1") (pintype "passive"))
    )
    (net (code "117") (name "Net-(DD8-QE23)") (class "Default")
      (node (ref "DD8") (pin "37") (pinfunction "QE23_37") (pintype "passive"))
      (node (ref "R104") (pin "1") (pinfunction "1_1") (pintype "passive"))
    )
    (net (code "118") (name "Net-(DD8-QO0)") (class "Default")
      (node (ref "DD8") (pin "49") (pinfunction "QO0_49") (pintype "passive"))
      (node (ref "R101") (pin "1") (pinfunction "1_1") (pintype "passive"))
    )
    (net (code "119") (name "Net-(DD8-QO1)") (class "Default")
      (node (ref "DD8") (pin "50") (pinfunction "QO1_50") (pintype "passive"))
      (node (ref "R100") (pin "1") (pinfunction "1_1") (pintype "passive"))
    )
    (net (code "120") (name "Net-(DD8-QO2)") (class "Default")
      (node (ref "DD8") (pin "51") (pinfunction "QO2_51") (pintype "passive"))
      (node (ref "R99") (pin "1") (pinfunction "1_1") (pintype "passive"))
    )
    (net (code "121") (name "Net-(DD8-QO3)") (class "Default")
      (node (ref "DD8") (pin "52") (pinfunction "QO3_52") (pintype "passive"))
      (node (ref "R98") (pin "1") (pinfunction "1_1") (pintype "passive"))
    )
    (net (code "122") (name "Net-(DD8-QO4)") (class "Default")
      (node (ref "DD8") (pin "53") (pinfunction "QO4_53") (pintype "passive"))
      (node (ref "R97") (pin "1") (pinfunction "1_1") (pintype "passive"))
    )
    (net (code "123") (name "Net-(DD8-QO5)") (class "Default")
      (node (ref "DD8") (pin "54") (pinfunction "QO5_54") (pintype "passive"))
      (node (ref "R96") (pin "1") (pinfunction "1_1") (pintype "passive"))
    )
    (net (code "124") (name "Net-(DD8-QO6)") (class "Default")
      (node (ref "DD8") (pin "55") (pinfunction "QO6_55") (pintype "passive"))
      (node (ref "R95") (pin "1") (pinfunction "1_1") (pintype "passive"))
    )
    (net (code "125") (name "Net-(DD8-QO7)") (class "Default")
      (node (ref "DD8") (pin "56") (pinfunction "QO7_56") (pintype "passive"))
      (node (ref "R94") (pin "1") (pinfunction "1_1") (pintype "passive"))
    )
    (net (code "126") (name "Net-(DD8-QO8)") (class "Default")
      (node (ref "DD8") (pin "59") (pinfunction "QO8_59") (pintype "passive"))
      (node (ref "R85") (pin "1") (pinfunction "1_1") (pintype "passive"))
    )
    (net (code "127") (name "Net-(DD8-QO9)") (class "Default")
      (node (ref "DD8") (pin "60") (pinfunction "QO9_60") (pintype "passive"))
      (node (ref "R84") (pin "1") (pinfunction "1_1") (pintype "passive"))
    )
    (net (code "128") (name "Net-(DD8-QO10)") (class "Default")
      (node (ref "DD8") (pin "61") (pinfunction "QO10_61") (pintype "passive"))
      (node (ref "R83") (pin "1") (pinfunction "1_1") (pintype "passive"))
    )
    (net (code "129") (name "Net-(DD8-QO11)") (class "Default")
      (node (ref "DD8") (pin "62") (pinfunction "QO11_62") (pintype "passive"))
      (node (ref "R82") (pin "1") (pinfunction "1_1") (pintype "passive"))
    )
    (net (code "130") (name "Net-(DD8-QO12)") (class "Default")
      (node (ref "DD8") (pin "63") (pinfunction "QO12_63") (pintype "passive"))
      (node (ref "R81") (pin "1") (pinfunction "1_1") (pintype "passive"))
    )
    (net (code "131") (name "Net-(DD8-QO13)") (class "Default")
      (node (ref "DD8") (pin "64") (pinfunction "QO13_64") (pintype "passive"))
      (node (ref "R80") (pin "1") (pinfunction "1_1") (pintype "passive"))
    )
    (net (code "132") (name "Net-(DD8-QO14)") (class "Default")
      (node (ref "DD8") (pin "65") (pinfunction "QO14_65") (pintype "passive"))
      (node (ref "R79") (pin "1") (pinfunction "1_1") (pintype "passive"))
    )
    (net (code "133") (name "Net-(DD8-QO15)") (class "Default")
      (node (ref "DD8") (pin "66") (pinfunction "QO15_66") (pintype "passive"))
      (node (ref "R78") (pin "1") (pinfunction "1_1") (pintype "passive"))
    )
    (net (code "134") (name "Net-(DD8-QO16)") (class "Default")
      (node (ref "DD8") (pin "69") (pinfunction "QO16_69") (pintype "passive"))
      (node (ref "R69") (pin "1") (pinfunction "1_1") (pintype "passive"))
    )
    (net (code "135") (name "Net-(DD8-QO17)") (class "Default")
      (node (ref "DD8") (pin "70") (pinfunction "QO17_70") (pintype "passive"))
      (node (ref "R68") (pin "1") (pinfunction "1_1") (pintype "passive"))
    )
    (net (code "136") (name "Net-(DD8-QO18)") (class "Default")
      (node (ref "DD8") (pin "71") (pinfunction "QO18_71") (pintype "passive"))
      (node (ref "R67") (pin "1") (pinfunction "1_1") (pintype "passive"))
    )
    (net (code "137") (name "Net-(DD8-QO19)") (class "Default")
      (node (ref "DD8") (pin "72") (pinfunction "QO19_72") (pintype "passive"))
      (node (ref "R65") (pin "1") (pinfunction "1_1") (pintype "passive"))
    )
    (net (code "138") (name "Net-(DD8-QO20)") (class "Default")
      (node (ref "DD8") (pin "73") (pinfunction "QO20_73") (pintype "passive"))
      (node (ref "R64") (pin "1") (pinfunction "1_1") (pintype "passive"))
    )
    (net (code "139") (name "Net-(DD8-QO21)") (class "Default")
      (node (ref "DD8") (pin "74") (pinfunction "QO21_74") (pintype "passive"))
      (node (ref "R60") (pin "1") (pinfunction "1_1") (pintype "passive"))
    )
    (net (code "140") (name "Net-(DD8-QO22)") (class "Default")
      (node (ref "DD8") (pin "75") (pinfunction "QO22_75") (pintype "passive"))
      (node (ref "R57") (pin "1") (pinfunction "1_1") (pintype "passive"))
    )
    (net (code "141") (name "Net-(DD8-QO23)") (class "Default")
      (node (ref "DD8") (pin "77") (pinfunction "QO23_77") (pintype "passive"))
      (node (ref "R56") (pin "1") (pinfunction "1_1") (pintype "passive"))
    )
    (net (code "142") (name "Net-(DD8-RX0+)") (class "Default")
      (node (ref "DD8") (pin "90") (pinfunction "RX0+_90") (pintype "passive"))
      (node (ref "RX_D5") (pin "1") (pinfunction "1_1") (pintype "passive"))
    )
    (net (code "143") (name "Net-(DD8-RX0-)") (class "Default")
      (node (ref "DD8") (pin "91") (pinfunction "RX0-_91") (pintype "passive"))
      (node (ref "RX_D6") (pin "1") (pinfunction "1_1") (pintype "passive"))
    )
    (net (code "144") (name "Net-(DD8-RX1+)") (class "Default")
      (node (ref "DD8") (pin "85") (pinfunction "RX1+_85") (pintype "passive"))
      (node (ref "RX_D3") (pin "1") (pinfunction "1_1") (pintype "passive"))
    )
    (net (code "145") (name "Net-(DD8-RX1-)") (class "Default")
      (node (ref "DD8") (pin "86") (pinfunction "RX1-_86") (pintype "passive"))
      (node (ref "RX_D4") (pin "1") (pinfunction "1_1") (pintype "passive"))
    )
    (net (code "146") (name "Net-(DD8-RX2+)") (class "Default")
      (node (ref "DD8") (pin "80") (pinfunction "RX2+_80") (pintype "passive"))
      (node (ref "RX_D1") (pin "1") (pinfunction "1_1") (pintype "passive"))
    )
    (net (code "147") (name "Net-(DD8-RX2-)") (class "Default")
      (node (ref "DD8") (pin "81") (pinfunction "RX2-_81") (pintype "passive"))
      (node (ref "RX_D2") (pin "1") (pinfunction "1_1") (pintype "passive"))
    )
    (net (code "148") (name "Net-(DD8-RXC+)") (class "Default")
      (node (ref "DD8") (pin "93") (pinfunction "RXC+_93") (pintype "passive"))
      (node (ref "RX_CLK+1") (pin "1") (pinfunction "1_1") (pintype "passive"))
    )
    (net (code "149") (name "Net-(DD8-RXC-)") (class "Default")
      (node (ref "DD8") (pin "94") (pinfunction "RXC-_94") (pintype "passive"))
      (node (ref "RX_CLK-1") (pin "1") (pinfunction "1_1") (pintype "passive"))
    )
    (net (code "150") (name "Net-(DD8-SCDT)") (class "Default")
      (node (ref "DD8") (pin "8") (pinfunction "SCDT_8") (pintype "passive"))
      (node (ref "R58") (pin "1") (pinfunction "1_1") (pintype "passive"))
      (node (ref "R66") (pin "2") (pinfunction "2_2") (pintype "passive"))
    )
    (net (code "151") (name "Net-(DD9-3Y0)") (class "Default")
      (node (ref "DD9") (pin "5") (pinfunction "3Y0_5") (pintype "passive"))
      (node (ref "R112") (pin "2") (pinfunction "2_2") (pintype "passive"))
    )
    (net (code "152") (name "Net-(DD9-3Y1)") (class "Default")
      (node (ref "DD9") (pin "3") (pinfunction "3Y1_3") (pintype "passive"))
      (node (ref "R113") (pin "2") (pinfunction "2_2") (pintype "passive"))
    )
    (net (code "153") (name "Net-(DD9-3Z)") (class "Default")
      (node (ref "DD9") (pin "4") (pinfunction "3Z_4") (pintype "passive"))
      (node (ref "R114") (pin "1") (pinfunction "1_1") (pintype "passive"))
    )
    (net (code "154") (name "O3_3V") (class "Default")
      (node (ref "C44") (pin "1") (pinfunction "1_1") (pintype "passive"))
      (node (ref "C47") (pin "2") (pinfunction "2_2") (pintype "passive"))
      (node (ref "C50") (pin "2") (pinfunction "2_2") (pintype "passive"))
      (node (ref "C53") (pin "2") (pinfunction "2_2") (pintype "passive"))
      (node (ref "C55") (pin "2") (pinfunction "2_2") (pintype "passive"))
      (node (ref "C57") (pin "2") (pinfunction "2_2") (pintype "passive"))
      (node (ref "DD8") (pin "18") (pinfunction "OVCC_18") (pintype "passive"))
      (node (ref "DD8") (pin "29") (pinfunction "OVCC_29") (pintype "passive"))
      (node (ref "DD8") (pin "43") (pinfunction "OVCC_43") (pintype "passive"))
      (node (ref "DD8") (pin "57") (pinfunction "OVCC_57") (pintype "passive"))
      (node (ref "DD8") (pin "78") (pinfunction "OVCC_78") (pintype "passive"))
      (node (ref "L14") (pin "2") (pinfunction "2_2") (pintype "passive"))
    )
    (net (code "155") (name "OSD_CLK") (class "Default")
      (node (ref "C58") (pin "1") (pinfunction "1_1") (pintype "passive"))
      (node (ref "R62") (pin "2") (pinfunction "2_2") (pintype "passive"))
      (node (ref "R63") (pin "2") (pinfunction "2_2") (pintype "passive"))
    )
    (net (code "156") (name "P3V3") (class "Default")
      (node (ref "R54") (pin "1") (pinfunction "1_1") (pintype "passive"))
      (node (ref "R55") (pin "1") (pinfunction "1_1") (pintype "passive"))
    )
    (net (code "157") (name "P3_3V") (class "Default")
      (node (ref "C42") (pin "1") (pinfunction "1_1") (pintype "passive"))
      (node (ref "C45") (pin "2") (pinfunction "2_2") (pintype "passive"))
      (node (ref "L15") (pin "2") (pinfunction "2_2") (pintype "passive"))
    )
    (net (code "158") (name "PKA_GND") (class "Default")
      (node (ref "DD8") (pin "79") (pinfunction "AGND_79") (pintype "passive"))
      (node (ref "DD8") (pin "83") (pinfunction "AGND_83") (pintype "passive"))
      (node (ref "DD8") (pin "87") (pinfunction "AGND_87") (pintype "passive"))
      (node (ref "DD8") (pin "89") (pinfunction "AGND_89") (pintype "passive"))
      (node (ref "DD8") (pin "92") (pinfunction "AGND_92") (pintype "passive"))
      (node (ref "L16") (pin "2") (pinfunction "2_2") (pintype "passive"))
      (node (ref "L17") (pin "2") (pinfunction "2_2") (pintype "passive"))
    )
    (net (code "159") (name "ROM_SCL") (class "Default")
      (node (ref "R112") (pin "1") (pinfunction "1_1") (pintype "passive"))
    )
    (net (code "160") (name "ROM_SCL_ASIC") (class "Default")
      (node (ref "R113") (pin "1") (pinfunction "1_1") (pintype "passive"))
    )
    (net (code "161") (name "VCLK01") (class "Default")
      (node (ref "R103") (pin "2") (pinfunction "2_2") (pintype "passive"))
    )
    (net (code "162") (name "VSYNC_D") (class "Default")
      (node (ref "DD8") (pin "47") (pinfunction "VSYNC_47") (pintype "passive"))
      (node (ref "DD9") (pin "2") (pinfunction "2Y0_2") (pintype "passive"))
    )
    (net (code "163") (name "unconnected-(DD5-NC-Pad1)") (class "Default")
      (node (ref "DD5") (pin "1") (pinfunction "NC_1") (pintype "passive"))
    )
    (net (code "164") (name "unconnected-(DD8-CTL1-Pad40)") (class "Default")
      (node (ref "DD8") (pin "40") (pinfunction "CTL1_40") (pintype "passive"))
    )
    (net (code "165") (name "unconnected-(DD8-CTL2-Pad41)") (class "Default")
      (node (ref "DD8") (pin "41") (pinfunction "CTL2_41") (pintype "passive"))
    )
    (net (code "166") (name "unconnected-(DD8-CTL3-Pad42)") (class "Default")
      (node (ref "DD8") (pin "42") (pinfunction "CTL3_42") (pintype "passive"))
    )
    (net (code "167") (name "unconnected-(DD8-PVCC-Pad97)") (class "Default")
      (node (ref "DD8") (pin "97") (pinfunction "PVCC_97") (pintype "passive"))
    )
    (net (code "168") (name "unconnected-(DD8-RESERVED-Pad99)") (class "Default")
      (node (ref "DD8") (pin "99") (pinfunction "RESERVED_99") (pintype "passive"))
    )
  )
)
